# 06-SX1276.net
KiCad netlist of a schematic drawn in Altium Designer
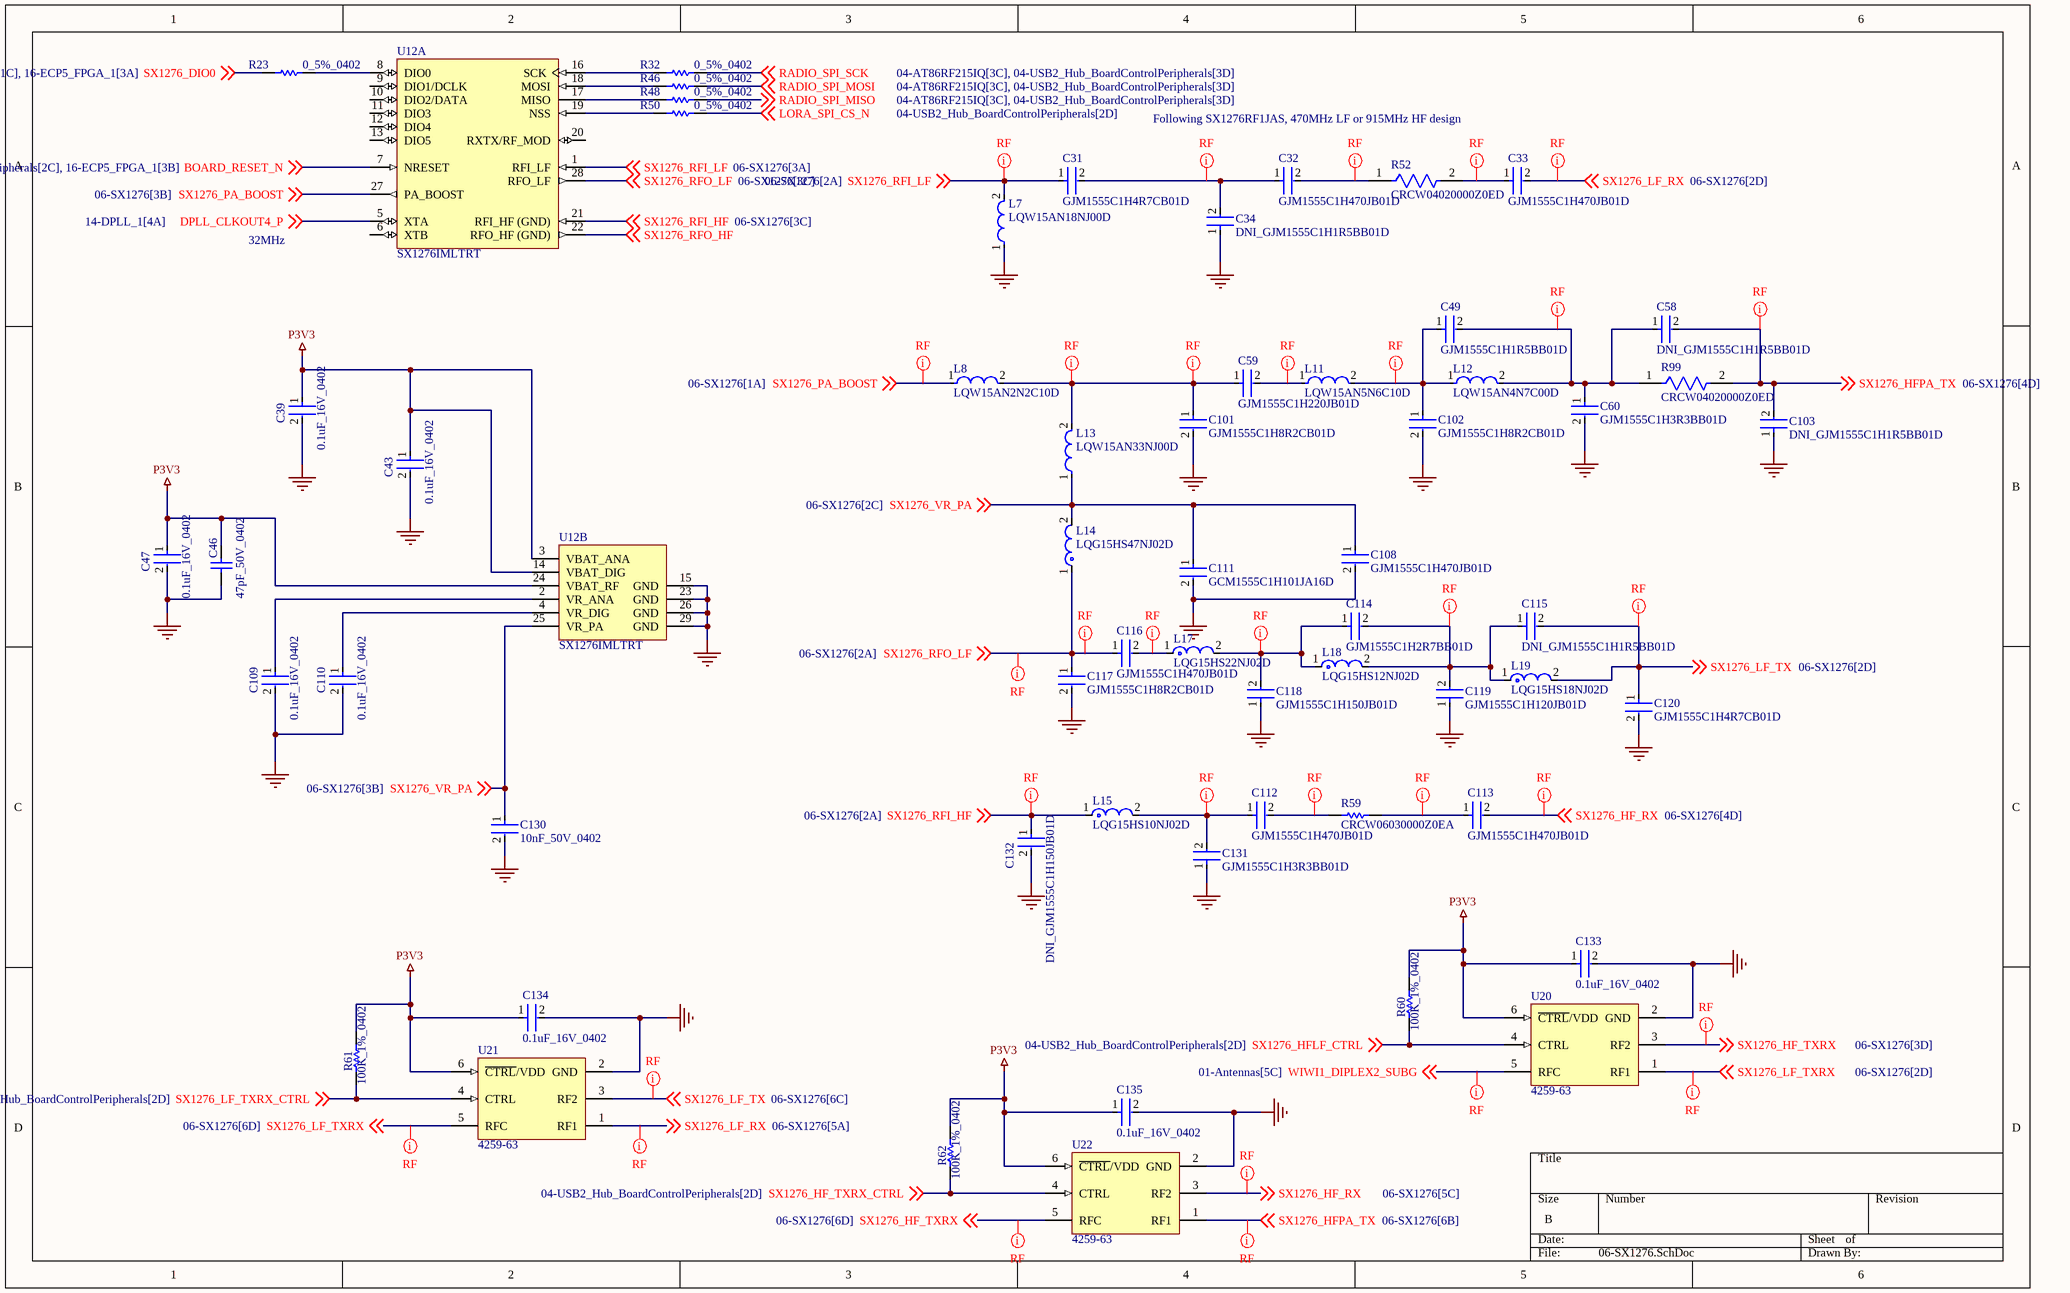
[diagram p0: 06-SX1276.SchDoc]

(export (version "E")
  (design (tool "Eeschema 10.0.6"))
  (components
    (comp (ref "C31")
      (value "GJM1555C1H4R7CB01D")
      (footprint "FP-GJM155-0_05-IPC_B")
      (description "Multi-Layer Ceramic Capacitor 4.7pF C0G  ±0.25pF 0402 Paper T/R")
      (fields (field (name "VOLTAGE") "50V"))
      (libsource (lib "Altium Content Vault") (part "02cd4be3c70576c341d710602a673aa"))
    )
    (comp (ref "C32")
      (value "GJM1555C1H470JB01D")
      (footprint "FP-GJM155-0_05-MFG")
      (description "Multi-Layer Ceramic Capacitor 47pF C0G  ±5% 0402 Paper T/R")
      (fields (field (name "TOLERANCE") "5%"))
      (libsource (lib "Altium Content Vault") (part "02cd4be3c70576c341d710602a673aa"))
    )
    (comp (ref "C33")
      (value "GJM1555C1H470JB01D")
      (footprint "FP-GJM155-0_05-MFG")
      (description "Multi-Layer Ceramic Capacitor 47pF C0G  ±5% 0402 Paper T/R")
      (fields (field (name "TOLERANCE") "5%"))
      (libsource (lib "Altium Content Vault") (part "02cd4be3c70576c341d710602a673aa"))
    )
    (comp (ref "C34")
      (value "DNI_GJM1555C1H1R5BB01D")
      (footprint "FP-GJM155-0_05-IPC_C")
      (description "Multi-Layer Ceramic Capacitor 1.5pF C0G  ±0.1pF 0402 Paper T/R")
      (fields (field (name "VOLTAGE") "50V"))
      (libsource (lib "Altium Content Vault") (part "02cd4be3c70576c341d710602a673aa"))
    )
    (comp (ref "C39")
      (value "0.1uF_16V_0402")
      (footprint "FP-C0402-BB-MFG")
      (description "CAP CER 0.1UF 16V 5% X7R 0402")
      (fields
        (field (name "MANUFACTURER") "Kemet")
        (field (name "MANUFACTURER PART NUMBER") "C0402C104J4RACTU")
      )
      (libsource (lib "Altium Content Vault") (part "b4654b650e69147ec39a6b967a45e02"))
    )
    (comp (ref "C43")
      (value "0.1uF_16V_0402")
      (footprint "FP-C0402-BB-MFG")
      (description "CAP CER 0.1UF 16V 5% X7R 0402")
      (fields
        (field (name "MANUFACTURER") "Kemet")
        (field (name "MANUFACTURER PART NUMBER") "C0402C104J4RACTU")
      )
      (libsource (lib "Altium Content Vault") (part "b4654b650e69147ec39a6b967a45e02"))
    )
    (comp (ref "C46")
      (value "47pF_50V_0402")
      (footprint "CAPC1005X55X25LL05T10")
      (fields (field (name "PART NUMBER") "GRM1555C1H470JA01D") (field (name "MANUFACTURER") "Murata"))
      (libsource (lib "Altium Content Vault") (part "CAP"))
    )
    (comp (ref "C47")
      (value "0.1uF_16V_0402")
      (footprint "FP-C0402-BB-MFG")
      (description "CAP CER 0.1UF 16V 5% X7R 0402")
      (fields
        (field (name "MANUFACTURER") "Kemet")
        (field (name "MANUFACTURER PART NUMBER") "C0402C104J4RACTU")
      )
      (libsource (lib "Altium Content Vault") (part "b4654b650e69147ec39a6b967a45e02"))
    )
    (comp (ref "C49")
      (value "GJM1555C1H1R5BB01D")
      (footprint "FP-GJM155-0_05-IPC_C")
      (description "Multi-Layer Ceramic Capacitor 1.5pF C0G  ±0.1pF 0402 Paper T/R")
      (fields (field (name "VOLTAGE") "50V"))
      (libsource (lib "Altium Content Vault") (part "02cd4be3c70576c341d710602a673aa"))
    )
    (comp (ref "C58")
      (value "DNI_GJM1555C1H1R5BB01D")
      (footprint "FP-GJM155-0_05-IPC_C")
      (description "Multi-Layer Ceramic Capacitor 1.5pF C0G  ±0.1pF 0402 Paper T/R")
      (fields (field (name "VOLTAGE") "50V"))
      (libsource (lib "Altium Content Vault") (part "02cd4be3c70576c341d710602a673aa"))
    )
    (comp (ref "C59")
      (value "GJM1555C1H220JB01D")
      (footprint "FP-GJM155-0_05-IPC_C")
      (description "Multi-Layer Ceramic Capacitor 22pF C0G  ±5% 0402 Paper T/R")
      (fields (field (name "TOLERANCE") "5%"))
      (libsource (lib "Altium Content Vault") (part "02cd4be3c70576c341d710602a673aa"))
    )
    (comp (ref "C60")
      (value "GJM1555C1H3R3BB01D")
      (footprint "FP-GJM155-0_05-IPC_C")
      (description "Multi-Layer Ceramic Capacitor 3.3pF C0G  ±0.1pF 0402 Paper T/R")
      (fields (field (name "VOLTAGE") "50V"))
      (libsource (lib "Altium Content Vault") (part "02cd4be3c70576c341d710602a673aa"))
    )
    (comp (ref "C101")
      (value "GJM1555C1H8R2CB01D")
      (footprint "FP-GJM155-0_05-IPC_C")
      (description "Multi-Layer Ceramic Capacitor 8.2pF C0G  ±0.25pF 0402 Paper T/R")
      (fields (field (name "VOLTAGE") "50V"))
      (libsource (lib "Altium Content Vault") (part "02cd4be3c70576c341d710602a673aa"))
    )
    (comp (ref "C102")
      (value "GJM1555C1H8R2CB01D")
      (footprint "FP-GJM155-0_05-IPC_C")
      (description "Multi-Layer Ceramic Capacitor 8.2pF C0G  ±0.25pF 0402 Paper T/R")
      (fields (field (name "VOLTAGE") "50V"))
      (libsource (lib "Altium Content Vault") (part "02cd4be3c70576c341d710602a673aa"))
    )
    (comp (ref "C103")
      (value "DNI_GJM1555C1H1R5BB01D")
      (footprint "FP-GJM155-0_05-IPC_C")
      (description "Multi-Layer Ceramic Capacitor 1.5pF C0G  ±0.1pF 0402 Paper T/R")
      (fields (field (name "VOLTAGE") "50V"))
      (libsource (lib "Altium Content Vault") (part "02cd4be3c70576c341d710602a673aa"))
    )
    (comp (ref "C108")
      (value "GJM1555C1H470JB01D")
      (footprint "FP-GJM155-0_05-MFG")
      (description "Multi-Layer Ceramic Capacitor 47pF C0G  ±5% 0402 Paper T/R")
      (fields (field (name "TOLERANCE") "5%"))
      (libsource (lib "Altium Content Vault") (part "02cd4be3c70576c341d710602a673aa"))
    )
    (comp (ref "C109")
      (value "0.1uF_16V_0402")
      (footprint "FP-C0402-BB-MFG")
      (description "CAP CER 0.1UF 16V 5% X7R 0402")
      (fields
        (field (name "MANUFACTURER") "Kemet")
        (field (name "MANUFACTURER PART NUMBER") "C0402C104J4RACTU")
      )
      (libsource (lib "Altium Content Vault") (part "b4654b650e69147ec39a6b967a45e02"))
    )
    (comp (ref "C110")
      (value "0.1uF_16V_0402")
      (footprint "FP-C0402-BB-MFG")
      (description "CAP CER 0.1UF 16V 5% X7R 0402")
      (fields
        (field (name "MANUFACTURER") "Kemet")
        (field (name "MANUFACTURER PART NUMBER") "C0402C104J4RACTU")
      )
      (libsource (lib "Altium Content Vault") (part "b4654b650e69147ec39a6b967a45e02"))
    )
    (comp (ref "C111")
      (value "GCM1555C1H101JA16D")
      (footprint "FP-GCM155-0_05-IPC_C")
      (description "Ceramic Capacitor for Automotive 100pF ±5% 50VDC C0G 0402 Paper T/R")
      (fields (field (name "VOLTAGE") "50V") (field (name "TOLERANCE") "5%"))
      (libsource (lib "Altium Content Vault") (part "02cd4be3c70576c341d710602a673aa"))
    )
    (comp (ref "C112")
      (value "GJM1555C1H470JB01D")
      (footprint "FP-GJM155-0_05-MFG")
      (description "Multi-Layer Ceramic Capacitor 47pF C0G  ±5% 0402 Paper T/R")
      (fields (field (name "TOLERANCE") "5%"))
      (libsource (lib "Altium Content Vault") (part "02cd4be3c70576c341d710602a673aa"))
    )
    (comp (ref "C113")
      (value "GJM1555C1H470JB01D")
      (footprint "FP-GJM155-0_05-MFG")
      (description "Multi-Layer Ceramic Capacitor 47pF C0G  ±5% 0402 Paper T/R")
      (fields (field (name "TOLERANCE") "5%"))
      (libsource (lib "Altium Content Vault") (part "02cd4be3c70576c341d710602a673aa"))
    )
    (comp (ref "C114")
      (value "GJM1555C1H2R7BB01D")
      (footprint "FP-GJM155-0_05-IPC_A")
      (description "Multi-Layer Ceramic Capacitor 2.7pF C0G  ±0.1pF 0402 Paper T/R")
      (fields (field (name "VOLTAGE") "50V"))
      (libsource (lib "Altium Content Vault") (part "02cd4be3c70576c341d710602a673aa"))
    )
    (comp (ref "C115")
      (value "DNI_GJM1555C1H1R5BB01D")
      (footprint "FP-GJM155-0_05-IPC_C")
      (description "Multi-Layer Ceramic Capacitor 1.5pF C0G  ±0.1pF 0402 Paper T/R")
      (fields (field (name "VOLTAGE") "50V"))
      (libsource (lib "Altium Content Vault") (part "02cd4be3c70576c341d710602a673aa"))
    )
    (comp (ref "C116")
      (value "GJM1555C1H470JB01D")
      (footprint "FP-GJM155-0_05-MFG")
      (description "Multi-Layer Ceramic Capacitor 47pF C0G  ±5% 0402 Paper T/R")
      (fields (field (name "TOLERANCE") "5%"))
      (libsource (lib "Altium Content Vault") (part "02cd4be3c70576c341d710602a673aa"))
    )
    (comp (ref "C117")
      (value "GJM1555C1H8R2CB01D")
      (footprint "FP-GJM155-0_05-IPC_C")
      (description "Multi-Layer Ceramic Capacitor 8.2pF C0G  ±0.25pF 0402 Paper T/R")
      (fields (field (name "VOLTAGE") "50V"))
      (libsource (lib "Altium Content Vault") (part "02cd4be3c70576c341d710602a673aa"))
    )
    (comp (ref "C118")
      (value "GJM1555C1H150JB01D")
      (footprint "FP-GJM155-0_05-IPC_A")
      (description "Multi-Layer Ceramic Capacitor 15pF C0G  ±5% 0402 Paper T/R")
      (fields (field (name "TOLERANCE") "5%") (field (name "VOLTAGE") "50V"))
      (libsource (lib "Altium Content Vault") (part "02cd4be3c70576c341d710602a673aa"))
    )
    (comp (ref "C119")
      (value "GJM1555C1H120JB01D")
      (footprint "FP-GJM155-0_05-IPC_A")
      (description "Multi-Layer Ceramic Capacitor 12pF C0G  ±5% 0402 Paper T/R")
      (fields (field (name "TOLERANCE") "5%") (field (name "VOLTAGE") "50V"))
      (libsource (lib "Altium Content Vault") (part "02cd4be3c70576c341d710602a673aa"))
    )
    (comp (ref "C120")
      (value "GJM1555C1H4R7CB01D")
      (footprint "FP-GJM155-0_05-IPC_B")
      (description "Multi-Layer Ceramic Capacitor 4.7pF C0G  ±0.25pF 0402 Paper T/R")
      (fields (field (name "VOLTAGE") "50V"))
      (libsource (lib "Altium Content Vault") (part "02cd4be3c70576c341d710602a673aa"))
    )
    (comp (ref "C130")
      (value "10nF_50V_0402")
      (footprint "FP-CL165-IPC_C")
      (description "Cap Ceramic 10nF 50V X7R ±10% SMD 0402 +125°C Paper T/R")
      (fields (field (name "VOLTAGE") "50V") (field (name "TOLERANCE") "10%"))
      (libsource (lib "Altium Content Vault") (part "b4654b650e69147ec39a6b967a45e02"))
    )
    (comp (ref "C131")
      (value "GJM1555C1H3R3BB01D")
      (footprint "FP-GJM155-0_05-IPC_C")
      (description "Multi-Layer Ceramic Capacitor 3.3pF C0G  ±0.1pF 0402 Paper T/R")
      (fields (field (name "VOLTAGE") "50V"))
      (libsource (lib "Altium Content Vault") (part "02cd4be3c70576c341d710602a673aa"))
    )
    (comp (ref "C132")
      (value "DNI_GJM1555C1H150JB01D")
      (footprint "FP-GJM155-0_05-IPC_A")
      (description "Multi-Layer Ceramic Capacitor 15pF C0G  ±5% 0402 Paper T/R")
      (fields (field (name "TOLERANCE") "5%") (field (name "VOLTAGE") "50V"))
      (libsource (lib "Altium Content Vault") (part "02cd4be3c70576c341d710602a673aa"))
    )
    (comp (ref "C133")
      (value "0.1uF_16V_0402")
      (footprint "FP-C0402-BB-MFG")
      (description "CAP CER 0.1UF 16V 5% X7R 0402")
      (fields
        (field (name "MANUFACTURER") "Kemet")
        (field (name "MANUFACTURER PART NUMBER") "C0402C104J4RACTU")
      )
      (libsource (lib "Altium Content Vault") (part "b4654b650e69147ec39a6b967a45e02"))
    )
    (comp (ref "C134")
      (value "0.1uF_16V_0402")
      (footprint "FP-C0402-BB-MFG")
      (description "CAP CER 0.1UF 16V 5% X7R 0402")
      (fields
        (field (name "MANUFACTURER") "Kemet")
        (field (name "MANUFACTURER PART NUMBER") "C0402C104J4RACTU")
      )
      (libsource (lib "Altium Content Vault") (part "b4654b650e69147ec39a6b967a45e02"))
    )
    (comp (ref "C135")
      (value "0.1uF_16V_0402")
      (footprint "FP-C0402-BB-MFG")
      (description "CAP CER 0.1UF 16V 5% X7R 0402")
      (fields
        (field (name "MANUFACTURER") "Kemet")
        (field (name "MANUFACTURER PART NUMBER") "C0402C104J4RACTU")
      )
      (libsource (lib "Altium Content Vault") (part "b4654b650e69147ec39a6b967a45e02"))
    )
    (comp (ref "L7")
      (value "LQW15AN18NJ00D")
      (footprint "FP-LQW15AN_00-W0_6-0_1-MFG")
      (description "Wire Wound RF Inductor 18nH ±5% 370mA 0.27Ω 0402 (1005)")
      (fields (field (name "TOLERANCE") "5%"))
      (libsource (lib "Altium Content Vault") (part "725321dda6339637d4d059423bc1c3c"))
    )
    (comp (ref "L8")
      (value "LQW15AN2N2C10D")
      (footprint "FP-LQW15AN_00-W0_6-0_1-MFG")
      (description "Wire Wound RF Inductor 2.2nH ±0.2nH 1000mA 0.027Ω 0402 (1005)")
      (libsource (lib "Altium Content Vault") (part "725321dda6339637d4d059423bc1c3c"))
    )
    (comp (ref "L11")
      (value "LQW15AN5N6C10D")
      (footprint "FP-LQW15AN_00-W0_6-0_1-MFG")
      (description "Wire Wound RF Inductor 5.6nH ±0.2nH 800mA 0.051Ω 0402 (1005)")
      (libsource (lib "Altium Content Vault") (part "725321dda6339637d4d059423bc1c3c"))
    )
    (comp (ref "L12")
      (value "LQW15AN4N7C00D")
      (footprint "FP-LQW15AN_00-W0_6-0_1-MFG")
      (description "Wire Wound RF Inductor 4.7nH ±0.2nH 750mA 0.07Ω 0402 (1005)")
      (libsource (lib "Altium Content Vault") (part "725321dda6339637d4d059423bc1c3c"))
    )
    (comp (ref "L13")
      (value "LQW15AN33NJ00D")
      (footprint "FP-LQW15AN_00-W0_5-0_1-MFG")
      (description "Wire Wound RF Inductor 33nH ±5% 260mA 0.63Ω 0402 (1005)")
      (fields (field (name "TOLERANCE") "5%"))
      (libsource (lib "Altium Content Vault") (part "725321dda6339637d4d059423bc1c3c"))
    )
    (comp (ref "L14")
      (value "LQG15HS47NJ02D")
      (footprint "FP-LQG15HH_02-IPC_B")
      (description "Multilayer type RF Inductor 47nH ±5% 0.72Ω 300mA 0402")
      (fields (field (name "TOLERANCE") "5%"))
      (libsource (lib "Altium Content Vault") (part "4cc4b267dca4c8e51f7102f422741d8"))
    )
    (comp (ref "L15")
      (value "LQG15HS10NJ02D")
      (footprint "FP-LQG15HH_02-IPC_A")
      (description "Multilayer type RF Inductor 10nH ±5% 0.26Ω 500mA 0402")
      (fields (field (name "TOLERANCE") "5%"))
      (libsource (lib "Altium Content Vault") (part "4cc4b267dca4c8e51f7102f422741d8"))
    )
    (comp (ref "L17")
      (value "LQG15HS22NJ02D")
      (footprint "FP-LQG15HH_02-MFG")
      (description "Multilayer type RF Inductor 22nH ±5% 0.42Ω 350mA 0402")
      (fields (field (name "TOLERANCE") "5%"))
      (libsource (lib "Altium Content Vault") (part "4cc4b267dca4c8e51f7102f422741d8"))
    )
    (comp (ref "L18")
      (value "LQG15HS12NJ02D")
      (footprint "FP-LQG15HH_02-IPC_A")
      (description "Multilayer type RF Inductor 12nH ±5% 0.28Ω 500mA 0402")
      (fields (field (name "TOLERANCE") "5%"))
      (libsource (lib "Altium Content Vault") (part "4cc4b267dca4c8e51f7102f422741d8"))
    )
    (comp (ref "L19")
      (value "LQG15HS18NJ02D")
      (footprint "FP-LQG15HH_02-MFG")
      (description "Multilayer type RF Inductor 18nH ±5% 0.36Ω 400mA 0402")
      (fields (field (name "TOLERANCE") "5%"))
      (libsource (lib "Altium Content Vault") (part "4cc4b267dca4c8e51f7102f422741d8"))
    )
    (comp (ref "R23")
      (value "0_5%_0402")
      (footprint "RESC1005X40X25NL05T10")
      (fields (field (name "MANUFACTURER") "Panasonic") (field (name "PART NUMBER") "ERJ-U020R00X"))
      (libsource (lib "Altium Content Vault") (part "RES"))
    )
    (comp (ref "R32")
      (value "0_5%_0402")
      (footprint "RESC1005X40X25NL05T10")
      (fields (field (name "MANUFACTURER") "Panasonic") (field (name "PART NUMBER") "ERJ-U020R00X"))
      (libsource (lib "Altium Content Vault") (part "RES"))
    )
    (comp (ref "R46")
      (value "0_5%_0402")
      (footprint "RESC1005X40X25NL05T10")
      (fields (field (name "MANUFACTURER") "Panasonic") (field (name "PART NUMBER") "ERJ-U020R00X"))
      (libsource (lib "Altium Content Vault") (part "RES"))
    )
    (comp (ref "R48")
      (value "0_5%_0402")
      (footprint "RESC1005X40X25NL05T10")
      (fields (field (name "MANUFACTURER") "Panasonic") (field (name "PART NUMBER") "ERJ-U020R00X"))
      (libsource (lib "Altium Content Vault") (part "RES"))
    )
    (comp (ref "R50")
      (value "0_5%_0402")
      (footprint "RESC1005X40X25NL05T10")
      (fields (field (name "MANUFACTURER") "Panasonic") (field (name "PART NUMBER") "ERJ-U020R00X"))
      (libsource (lib "Altium Content Vault") (part "RES"))
    )
    (comp (ref "R52")
      (value "CRCW04020000Z0ED")
      (footprint "FP-CRCW0402-e3-IPC_C")
      (description "RES Thick Film, 0Ω, 0.063W, 0402")
      (fields (field (name "TOLERANCE") "5%"))
      (libsource (lib "Altium Content Vault") (part "1029c3af85768c4190bb7ad29bc67b5"))
    )
    (comp (ref "R59")
      (value "CRCW06030000Z0EA")
      (footprint "RESC1609X50X30NL8T20")
      (description "Chip Resistor, 0 Ohm, Jumper, 100 mW, -55 to 155 degC, 0603 (1608 Metric), RoHS, Tape and Reel")
      (fields (field (name "MANUFACTURER") "Vishay Semiconductor"))
      (libsource (lib "Altium Content Vault") (part "RES-2"))
    )
    (comp (ref "R60")
      (value "100K_1%_0402")
      (footprint "RESC1005X40X25ML05T10")
      (fields (field (name "MANUFACTURER") "Yageo") (field (name "PART NUMBER") "RC0402FR-13100KL"))
      (libsource (lib "Altium Content Vault") (part "RES"))
    )
    (comp (ref "R61")
      (value "100K_1%_0402")
      (footprint "RESC1005X40X25ML05T10")
      (fields (field (name "MANUFACTURER") "Yageo") (field (name "PART NUMBER") "RC0402FR-13100KL"))
      (libsource (lib "Altium Content Vault") (part "RES"))
    )
    (comp (ref "R62")
      (value "100K_1%_0402")
      (footprint "RESC1005X40X25ML05T10")
      (fields (field (name "MANUFACTURER") "Yageo") (field (name "PART NUMBER") "RC0402FR-13100KL"))
      (libsource (lib "Altium Content Vault") (part "RES"))
    )
    (comp (ref "R99")
      (value "CRCW04020000Z0ED")
      (footprint "FP-CRCW0402-e3-IPC_C")
      (description "RES Thick Film, 0Ω, 0.063W, 0402")
      (fields (field (name "TOLERANCE") "5%"))
      (libsource (lib "Altium Content Vault") (part "1029c3af85768c4190bb7ad29bc67b5"))
    )
    (comp (ref "U12")
      (value "SX1276IMLTRT")
      (footprint "SMTC-QFN-28_V")
      (description "Low Power Long Range Transceiver, 137 to 1020 MHz, -40 to 85 degC, 28-Pin QFN, RoHS, Tape and Reel")
      (fields (field (name "MANUFACTURER") "Semtech"))
      (libsource (lib "Altium Content Vault") (part "SMTC-SX127X-QFN-28"))
    )
    (comp (ref "U20")
      (value "4259-63")
      (footprint "PERE-SC-70-6_M")
      (description "IC RF Switch SPDT, 50 Ohm, 6-Pin SC70, RoHS, Tape and Reel")
      (fields (field (name "MANUFACTURER") "Peregrine Semiconductor"))
      (libsource (lib "Altium Content Vault") (part "PERE-PE4259-6"))
    )
    (comp (ref "U21")
      (value "4259-63")
      (footprint "PERE-SC-70-6_M")
      (description "IC RF Switch SPDT, 50 Ohm, 6-Pin SC70, RoHS, Tape and Reel")
      (fields (field (name "MANUFACTURER") "Peregrine Semiconductor"))
      (libsource (lib "Altium Content Vault") (part "PERE-PE4259-6"))
    )
    (comp (ref "U22")
      (value "4259-63")
      (footprint "PERE-SC-70-6_M")
      (description "IC RF Switch SPDT, 50 Ohm, 6-Pin SC70, RoHS, Tape and Reel")
      (fields (field (name "MANUFACTURER") "Peregrine Semiconductor"))
      (libsource (lib "Altium Content Vault") (part "PERE-PE4259-6"))
    )
  )
  (nets
    (net (code "1") (name "BOARD_RESET_N") (class "Default")
      (node (ref "U12") (pin "7") (pinfunction "NRESET_7") (pintype "input"))
    )
    (net (code "2") (name "DPLL_CLKOUT4_P") (class "Default")
      (node (ref "U12") (pin "5") (pinfunction "XTA_5") (pintype "bidirectional"))
    )
    (net (code "3") (name "GND") (class "Default")
      (node (ref "C101") (pin "2") (pinfunction "2_2") (pintype "passive"))
      (node (ref "C102") (pin "2") (pinfunction "2_2") (pintype "passive"))
      (node (ref "C103") (pin "1") (pinfunction "1_1") (pintype "passive"))
      (node (ref "C108") (pin "2") (pinfunction "2_2") (pintype "passive"))
      (node (ref "C109") (pin "2") (pinfunction "2_2") (pintype "passive"))
      (node (ref "C110") (pin "2") (pinfunction "2_2") (pintype "passive"))
      (node (ref "C111") (pin "2") (pinfunction "2_2") (pintype "passive"))
      (node (ref "C117") (pin "2") (pinfunction "2_2") (pintype "passive"))
      (node (ref "C118") (pin "1") (pinfunction "1_1") (pintype "passive"))
      (node (ref "C119") (pin "1") (pinfunction "1_1") (pintype "passive"))
      (node (ref "C120") (pin "2") (pinfunction "2_2") (pintype "passive"))
      (node (ref "C130") (pin "2") (pinfunction "2_2") (pintype "passive"))
      (node (ref "C131") (pin "1") (pinfunction "1_1") (pintype "passive"))
      (node (ref "C132") (pin "2") (pinfunction "2_2") (pintype "passive"))
      (node (ref "C133") (pin "2") (pinfunction "2_2") (pintype "passive"))
      (node (ref "C134") (pin "2") (pinfunction "2_2") (pintype "passive"))
      (node (ref "C135") (pin "2") (pinfunction "2_2") (pintype "passive"))
      (node (ref "C34") (pin "1") (pinfunction "1_1") (pintype "passive"))
      (node (ref "C39") (pin "2") (pinfunction "2_2") (pintype "passive"))
      (node (ref "C43") (pin "2") (pinfunction "2_2") (pintype "passive"))
      (node (ref "C46") (pin "1") (pinfunction "1_1") (pintype "passive"))
      (node (ref "C47") (pin "2") (pinfunction "2_2") (pintype "passive"))
      (node (ref "C60") (pin "2") (pinfunction "2_2") (pintype "passive"))
      (node (ref "L7") (pin "1") (pinfunction "1_1") (pintype "passive"))
      (node (ref "U12") (pin "15") (pinfunction "GND_15") (pintype "power_in"))
      (node (ref "U12") (pin "23") (pinfunction "GND_23") (pintype "power_in"))
      (node (ref "U12") (pin "26") (pinfunction "GND_26") (pintype "power_in"))
      (node (ref "U12") (pin "29") (pinfunction "GND_29") (pintype "power_in"))
      (node (ref "U20") (pin "2") (pinfunction "GND_2") (pintype "power_in"))
      (node (ref "U21") (pin "2") (pinfunction "GND_2") (pintype "power_in"))
      (node (ref "U22") (pin "2") (pinfunction "GND_2") (pintype "power_in"))
    )
    (net (code "4") (name "LORA_SPI_CS_N") (class "Default")
      (node (ref "R50") (pin "2") (pinfunction "2_2") (pintype "passive"))
    )
    (net (code "5") (name "Net-(C31-Pad2)") (class "Default")
      (node (ref "C31") (pin "2") (pinfunction "2_2") (pintype "passive"))
      (node (ref "C32") (pin "1") (pinfunction "1_1") (pintype "passive"))
      (node (ref "C34") (pin "2") (pinfunction "2_2") (pintype "passive"))
    )
    (net (code "6") (name "Net-(C32-Pad2)") (class "Default")
      (node (ref "C32") (pin "2") (pinfunction "2_2") (pintype "passive"))
      (node (ref "R52") (pin "1") (pinfunction "1_1") (pintype "passive"))
    )
    (net (code "7") (name "Net-(C33-Pad1)") (class "Default")
      (node (ref "C33") (pin "1") (pinfunction "1_1") (pintype "passive"))
      (node (ref "R52") (pin "2") (pinfunction "2_2") (pintype "passive"))
    )
    (net (code "8") (name "Net-(C49-Pad2)") (class "Default")
      (node (ref "C49") (pin "2") (pinfunction "2_2") (pintype "passive"))
      (node (ref "C58") (pin "1") (pinfunction "1_1") (pintype "passive"))
      (node (ref "C60") (pin "1") (pinfunction "1_1") (pintype "passive"))
      (node (ref "L12") (pin "2") (pinfunction "2_2") (pintype "passive"))
      (node (ref "R99") (pin "1") (pinfunction "1_1") (pintype "passive"))
    )
    (net (code "9") (name "Net-(C59-Pad2)") (class "Default")
      (node (ref "C59") (pin "2") (pinfunction "2_2") (pintype "passive"))
      (node (ref "L11") (pin "1") (pinfunction "1_1") (pintype "passive"))
    )
    (net (code "10") (name "Net-(C101-Pad1)") (class "Default")
      (node (ref "C101") (pin "1") (pinfunction "1_1") (pintype "passive"))
      (node (ref "C59") (pin "1") (pinfunction "1_1") (pintype "passive"))
      (node (ref "L13") (pin "2") (pinfunction "2_2") (pintype "passive"))
      (node (ref "L8") (pin "2") (pinfunction "2_2") (pintype "passive"))
    )
    (net (code "11") (name "Net-(C102-Pad1)") (class "Default")
      (node (ref "C102") (pin "1") (pinfunction "1_1") (pintype "passive"))
      (node (ref "C49") (pin "1") (pinfunction "1_1") (pintype "passive"))
      (node (ref "L11") (pin "2") (pinfunction "2_2") (pintype "passive"))
      (node (ref "L12") (pin "1") (pinfunction "1_1") (pintype "passive"))
    )
    (net (code "12") (name "Net-(C112-Pad1)") (class "Default")
      (node (ref "C112") (pin "1") (pinfunction "1_1") (pintype "passive"))
      (node (ref "C131") (pin "2") (pinfunction "2_2") (pintype "passive"))
      (node (ref "L15") (pin "2") (pinfunction "2_2") (pintype "passive"))
    )
    (net (code "13") (name "Net-(C112-Pad2)") (class "Default")
      (node (ref "C112") (pin "2") (pinfunction "2_2") (pintype "passive"))
      (node (ref "R59") (pin "1") (pinfunction "1_1") (pintype "passive"))
    )
    (net (code "14") (name "Net-(C113-Pad1)") (class "Default")
      (node (ref "C113") (pin "1") (pinfunction "1_1") (pintype "passive"))
      (node (ref "R59") (pin "2") (pinfunction "2_2") (pintype "passive"))
    )
    (net (code "15") (name "Net-(C114-Pad1)") (class "Default")
      (node (ref "C114") (pin "1") (pinfunction "1_1") (pintype "passive"))
      (node (ref "C118") (pin "2") (pinfunction "2_2") (pintype "passive"))
      (node (ref "L17") (pin "2") (pinfunction "2_2") (pintype "passive"))
      (node (ref "L18") (pin "1") (pinfunction "1_1") (pintype "passive"))
    )
    (net (code "16") (name "Net-(C114-Pad2)") (class "Default")
      (node (ref "C114") (pin "2") (pinfunction "2_2") (pintype "passive"))
      (node (ref "C115") (pin "1") (pinfunction "1_1") (pintype "passive"))
      (node (ref "C119") (pin "2") (pinfunction "2_2") (pintype "passive"))
      (node (ref "L18") (pin "2") (pinfunction "2_2") (pintype "passive"))
      (node (ref "L19") (pin "1") (pinfunction "1_1") (pintype "passive"))
    )
    (net (code "17") (name "Net-(C116-Pad2)") (class "Default")
      (node (ref "C116") (pin "2") (pinfunction "2_2") (pintype "passive"))
      (node (ref "L17") (pin "1") (pinfunction "1_1") (pintype "passive"))
    )
    (net (code "18") (name "Net-(U12A-DIO0)") (class "Default")
      (node (ref "R23") (pin "2") (pinfunction "2_2") (pintype "passive"))
      (node (ref "U12") (pin "8") (pinfunction "DIO0_8") (pintype "bidirectional"))
    )
    (net (code "19") (name "Net-(U12A-MISO)") (class "Default")
      (node (ref "R48") (pin "1") (pinfunction "1_1") (pintype "passive"))
      (node (ref "U12") (pin "17") (pinfunction "MISO_17") (pintype "tri_state"))
    )
    (net (code "20") (name "Net-(U12A-MOSI)") (class "Default")
      (node (ref "R46") (pin "1") (pinfunction "1_1") (pintype "passive"))
      (node (ref "U12") (pin "18") (pinfunction "MOSI_18") (pintype "input"))
    )
    (net (code "21") (name "Net-(U12A-NSS)") (class "Default")
      (node (ref "R50") (pin "1") (pinfunction "1_1") (pintype "passive"))
      (node (ref "U12") (pin "19") (pinfunction "NSS_19") (pintype "input"))
    )
    (net (code "22") (name "Net-(U12A-SCK)") (class "Default")
      (node (ref "R32") (pin "1") (pinfunction "1_1") (pintype "passive"))
      (node (ref "U12") (pin "16") (pinfunction "SCK_16") (pintype "input"))
    )
    (net (code "23") (name "Net-(U12B-VR_ANA)") (class "Default")
      (node (ref "C109") (pin "1") (pinfunction "1_1") (pintype "passive"))
      (node (ref "U12") (pin "2") (pinfunction "VR_ANA_2") (pintype "power_in"))
    )
    (net (code "24") (name "Net-(U12B-VR_DIG)") (class "Default")
      (node (ref "C110") (pin "1") (pinfunction "1_1") (pintype "passive"))
      (node (ref "U12") (pin "4") (pinfunction "VR_DIG_4") (pintype "power_in"))
    )
    (net (code "25") (name "P3V3") (class "Default")
      (node (ref "C133") (pin "1") (pinfunction "1_1") (pintype "passive"))
      (node (ref "C134") (pin "1") (pinfunction "1_1") (pintype "passive"))
      (node (ref "C135") (pin "1") (pinfunction "1_1") (pintype "passive"))
      (node (ref "C39") (pin "1") (pinfunction "1_1") (pintype "passive"))
      (node (ref "C43") (pin "1") (pinfunction "1_1") (pintype "passive"))
      (node (ref "C46") (pin "2") (pinfunction "2_2") (pintype "passive"))
      (node (ref "C47") (pin "1") (pinfunction "1_1") (pintype "passive"))
      (node (ref "R60") (pin "2") (pinfunction "2_2") (pintype "passive"))
      (node (ref "R61") (pin "2") (pinfunction "2_2") (pintype "passive"))
      (node (ref "R62") (pin "2") (pinfunction "2_2") (pintype "passive"))
      (node (ref "U12") (pin "14") (pinfunction "VBAT_DIG_14") (pintype "power_in"))
      (node (ref "U12") (pin "24") (pinfunction "VBAT_RF_24") (pintype "power_in"))
      (node (ref "U12") (pin "3") (pinfunction "VBAT_ANA_3") (pintype "power_in"))
      (node (ref "U20") (pin "6") (pinfunction "~{CTRL}/VDD_6") (pintype "input"))
      (node (ref "U21") (pin "6") (pinfunction "~{CTRL}/VDD_6") (pintype "input"))
      (node (ref "U22") (pin "6") (pinfunction "~{CTRL}/VDD_6") (pintype "input"))
    )
    (net (code "26") (name "RADIO_SPI_MISO") (class "Default")
      (node (ref "R48") (pin "2") (pinfunction "2_2") (pintype "passive"))
    )
    (net (code "27") (name "RADIO_SPI_MOSI") (class "Default")
      (node (ref "R46") (pin "2") (pinfunction "2_2") (pintype "passive"))
    )
    (net (code "28") (name "RADIO_SPI_SCK") (class "Default")
      (node (ref "R32") (pin "2") (pinfunction "2_2") (pintype "passive"))
    )
    (net (code "29") (name "SX1276_DIO0") (class "Default")
      (node (ref "R23") (pin "1") (pinfunction "1_1") (pintype "passive"))
    )
    (net (code "30") (name "SX1276_HFLF_CTRL") (class "Default")
      (node (ref "R60") (pin "1") (pinfunction "1_1") (pintype "passive"))
      (node (ref "U20") (pin "4") (pinfunction "CTRL_4") (pintype "input"))
    )
    (net (code "31") (name "SX1276_HFPA_TX") (class "Default")
      (node (ref "C103") (pin "2") (pinfunction "2_2") (pintype "passive"))
      (node (ref "C58") (pin "2") (pinfunction "2_2") (pintype "passive"))
      (node (ref "R99") (pin "2") (pinfunction "2_2") (pintype "passive"))
      (node (ref "U22") (pin "1") (pinfunction "RF1_1") (pintype "passive"))
    )
    (net (code "32") (name "SX1276_HF_RX") (class "Default")
      (node (ref "C113") (pin "2") (pinfunction "2_2") (pintype "passive"))
      (node (ref "U22") (pin "3") (pinfunction "RF2_3") (pintype "passive"))
    )
    (net (code "33") (name "SX1276_HF_TXRX") (class "Default")
      (node (ref "U20") (pin "3") (pinfunction "RF2_3") (pintype "passive"))
      (node (ref "U22") (pin "5") (pinfunction "RFC_5") (pintype "passive"))
    )
    (net (code "34") (name "SX1276_HF_TXRX_CTRL") (class "Default")
      (node (ref "R62") (pin "1") (pinfunction "1_1") (pintype "passive"))
      (node (ref "U22") (pin "4") (pinfunction "CTRL_4") (pintype "input"))
    )
    (net (code "35") (name "SX1276_LF_RX") (class "Default")
      (node (ref "C33") (pin "2") (pinfunction "2_2") (pintype "passive"))
      (node (ref "U21") (pin "1") (pinfunction "RF1_1") (pintype "passive"))
    )
    (net (code "36") (name "SX1276_LF_TX") (class "Default")
      (node (ref "C115") (pin "2") (pinfunction "2_2") (pintype "passive"))
      (node (ref "C120") (pin "1") (pinfunction "1_1") (pintype "passive"))
      (node (ref "L19") (pin "2") (pinfunction "2_2") (pintype "passive"))
      (node (ref "U21") (pin "3") (pinfunction "RF2_3") (pintype "passive"))
    )
    (net (code "37") (name "SX1276_LF_TXRX") (class "Default")
      (node (ref "U20") (pin "1") (pinfunction "RF1_1") (pintype "passive"))
      (node (ref "U21") (pin "5") (pinfunction "RFC_5") (pintype "passive"))
    )
    (net (code "38") (name "SX1276_LF_TXRX_CTRL") (class "Default")
      (node (ref "R61") (pin "1") (pinfunction "1_1") (pintype "passive"))
      (node (ref "U21") (pin "4") (pinfunction "CTRL_4") (pintype "input"))
    )
    (net (code "39") (name "SX1276_PA_BOOST") (class "Default")
      (node (ref "L8") (pin "1") (pinfunction "1_1") (pintype "passive"))
      (node (ref "U12") (pin "27") (pinfunction "PA_BOOST_27") (pintype "output"))
    )
    (net (code "40") (name "SX1276_RFI_HF") (class "Default")
      (node (ref "C132") (pin "1") (pinfunction "1_1") (pintype "passive"))
      (node (ref "L15") (pin "1") (pinfunction "1_1") (pintype "passive"))
      (node (ref "U12") (pin "21") (pinfunction "RFI_HF_(GND)_21") (pintype "input"))
    )
    (net (code "41") (name "SX1276_RFI_LF") (class "Default")
      (node (ref "C31") (pin "1") (pinfunction "1_1") (pintype "passive"))
      (node (ref "L7") (pin "2") (pinfunction "2_2") (pintype "passive"))
      (node (ref "U12") (pin "1") (pinfunction "RFI_LF_1") (pintype "input"))
    )
    (net (code "42") (name "SX1276_RFO_HF") (class "Default")
      (node (ref "U12") (pin "22") (pinfunction "RFO_HF_(GND)_22") (pintype "output"))
    )
    (net (code "43") (name "SX1276_RFO_LF") (class "Default")
      (node (ref "C116") (pin "1") (pinfunction "1_1") (pintype "passive"))
      (node (ref "C117") (pin "1") (pinfunction "1_1") (pintype "passive"))
      (node (ref "L14") (pin "1") (pinfunction "1_1") (pintype "passive"))
      (node (ref "U12") (pin "28") (pinfunction "RFO_LF_28") (pintype "output"))
    )
    (net (code "44") (name "SX1276_VR_PA") (class "Default")
      (node (ref "C108") (pin "1") (pinfunction "1_1") (pintype "passive"))
      (node (ref "C111") (pin "1") (pinfunction "1_1") (pintype "passive"))
      (node (ref "C130") (pin "1") (pinfunction "1_1") (pintype "passive"))
      (node (ref "L13") (pin "1") (pinfunction "1_1") (pintype "passive"))
      (node (ref "L14") (pin "2") (pinfunction "2_2") (pintype "passive"))
      (node (ref "U12") (pin "25") (pinfunction "VR_PA_25") (pintype "power_in"))
    )
    (net (code "45") (name "WIWI1_DIPLEX2_SUBG") (class "Default")
      (node (ref "U20") (pin "5") (pinfunction "RFC_5") (pintype "passive"))
    )
    (net (code "46") (name "unconnected-(U12A-DIO1{slash}DCLK-Pad9)") (class "Default")
      (node (ref "U12") (pin "9") (pinfunction "DIO1/DCLK_9") (pintype "bidirectional"))
    )
    (net (code "47") (name "unconnected-(U12A-DIO2{slash}DATA-Pad10)") (class "Default")
      (node (ref "U12") (pin "10") (pinfunction "DIO2/DATA_10") (pintype "bidirectional"))
    )
    (net (code "48") (name "unconnected-(U12A-DIO3-Pad11)") (class "Default")
      (node (ref "U12") (pin "11") (pinfunction "DIO3_11") (pintype "bidirectional"))
    )
    (net (code "49") (name "unconnected-(U12A-DIO4-Pad12)") (class "Default")
      (node (ref "U12") (pin "12") (pinfunction "DIO4_12") (pintype "bidirectional"))
    )
    (net (code "50") (name "unconnected-(U12A-DIO5-Pad13)") (class "Default")
      (node (ref "U12") (pin "13") (pinfunction "DIO5_13") (pintype "bidirectional"))
    )
    (net (code "51") (name "unconnected-(U12A-RXTX{slash}RF_MOD-Pad20)") (class "Default")
      (node (ref "U12") (pin "20") (pinfunction "RXTX/RF_MOD_20") (pintype "bidirectional"))
    )
    (net (code "52") (name "unconnected-(U12A-XTB-Pad6)") (class "Default")
      (node (ref "U12") (pin "6") (pinfunction "XTB_6") (pintype "bidirectional"))
    )
  )
)
